# SafetySwitchBoard.net
KiCad netlist of a schematic drawn in EAGLE
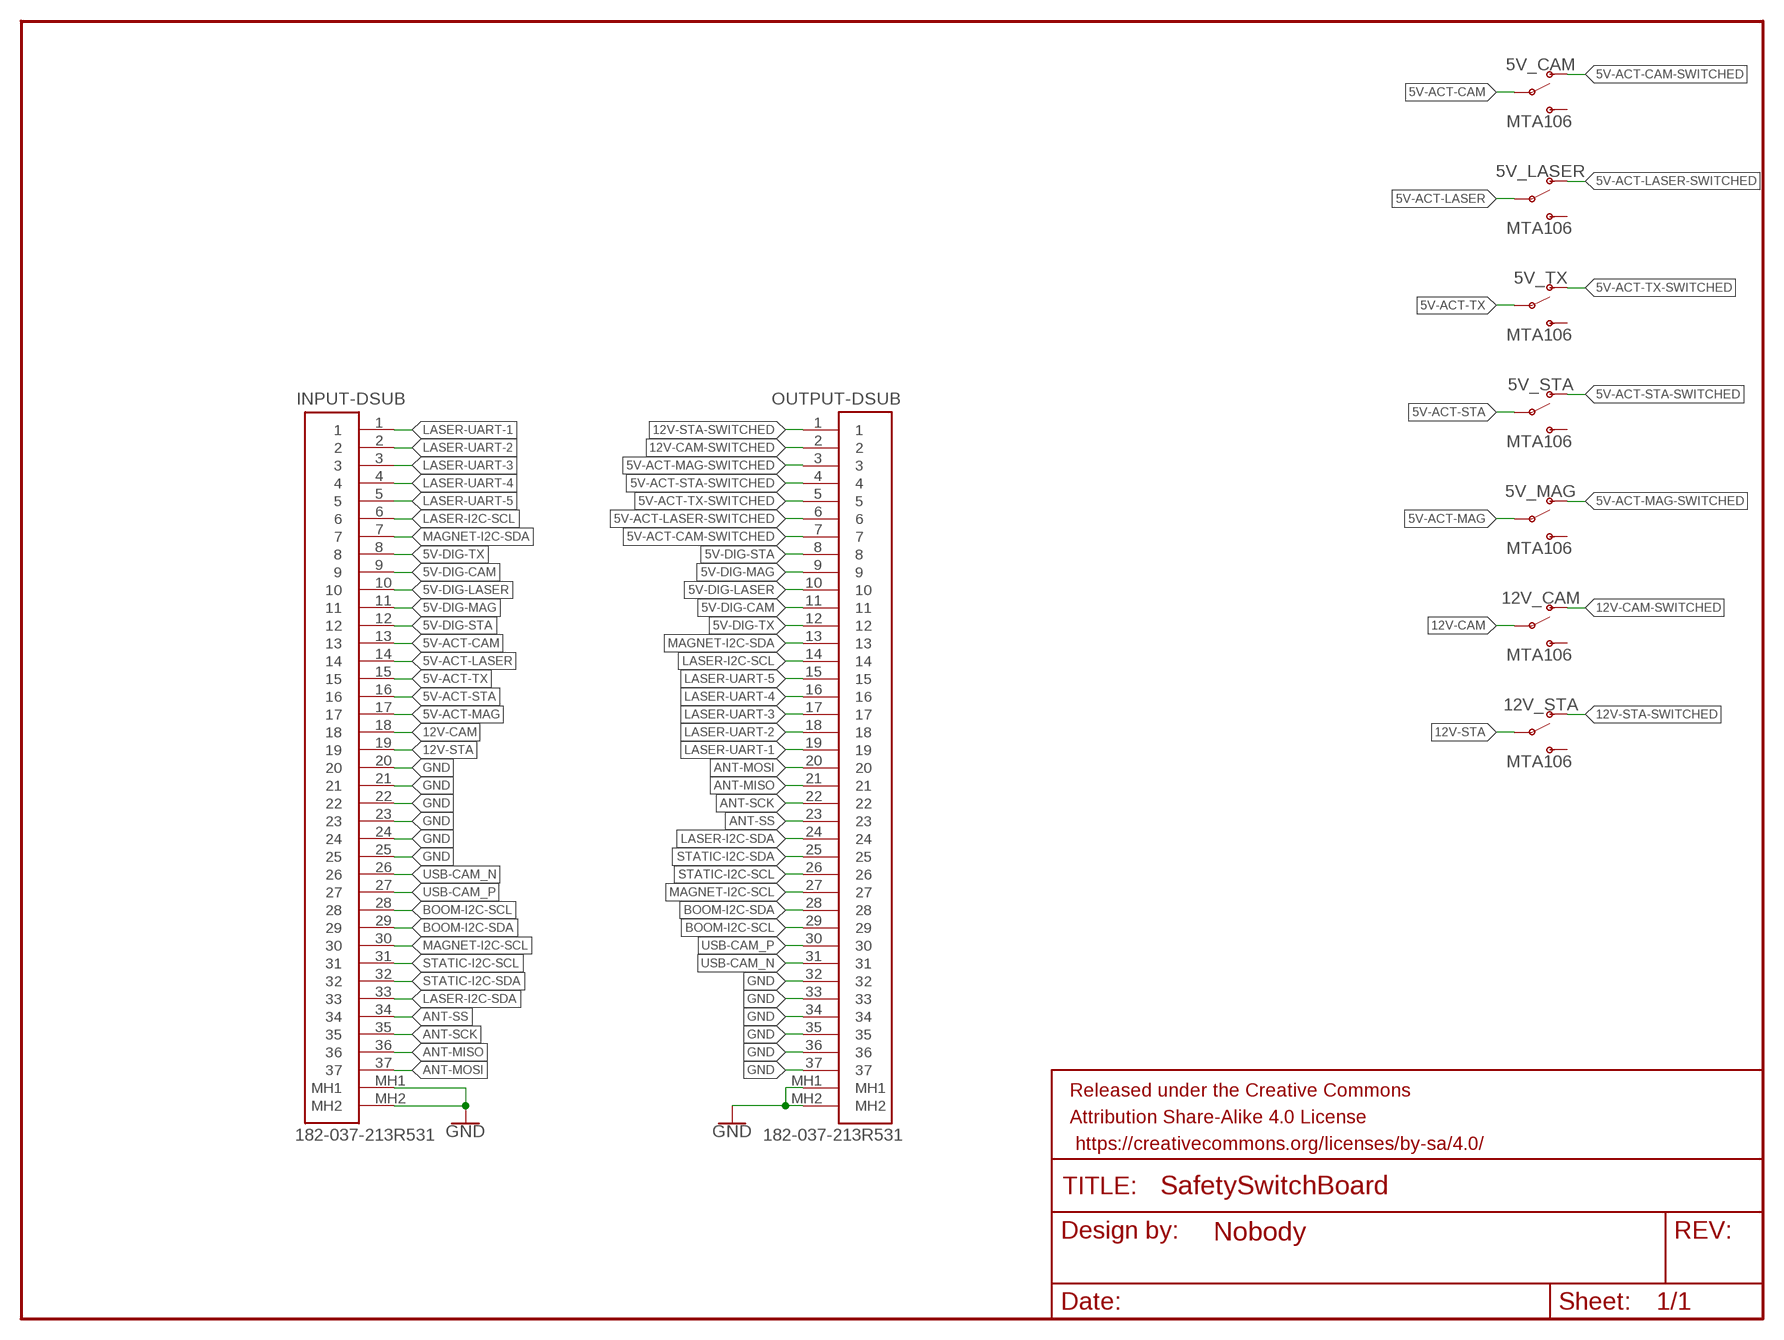
[diagram p0: schematic, sheet 1]

(export (version "E")
  (design (tool "Eeschema 10.0.6"))
  (components
    (comp (ref "5V_CAM")
      (value "MTA106")
      (footprint "eagle-import:MTA106")
      (libsource (lib "eagle-import") (part "MTA106"))
    )
    (comp (ref "5V_LASER")
      (value "MTA106")
      (footprint "eagle-import:MTA106")
      (libsource (lib "eagle-import") (part "MTA106"))
    )
    (comp (ref "5V_MAG")
      (value "MTA106")
      (footprint "eagle-import:MTA106")
      (libsource (lib "eagle-import") (part "MTA106"))
    )
    (comp (ref "5V_STA")
      (value "MTA106")
      (footprint "eagle-import:MTA106")
      (libsource (lib "eagle-import") (part "MTA106"))
    )
    (comp (ref "5V_TX")
      (value "MTA106")
      (footprint "eagle-import:MTA106")
      (libsource (lib "eagle-import") (part "MTA106"))
    )
    (comp (ref "12V_CAM")
      (value "MTA106")
      (footprint "eagle-import:MTA106")
      (libsource (lib "eagle-import") (part "MTA106"))
    )
    (comp (ref "12V_STA")
      (value "MTA106")
      (footprint "eagle-import:MTA106")
      (libsource (lib "eagle-import") (part "MTA106"))
    )
    (comp (ref "FRAME1")
      (value "FRAME-LETTERNO_PACKAGE")
      (footprint "eagle-import:DUMMY")
      (fields (field (name "DESIGNER") "Nobody"))
      (libsource (lib "eagle-import") (part "FRAME-LETTERNO_PACKAGE"))
    )
    (comp (ref "INPUT-DSUB")
      (value "182-037-213R531")
      (footprint "eagle-import:182-037-213R531")
      (fields
        (field (name "DIGI_KEY_PART_NUMBER") "182-37FE-ND")
        (field (name "MANUFACTURER") "NorComp Inc.")
        (field (name "CREATED_BY") "PCBLayout.com")
      )
      (libsource (lib "eagle-import") (part "182-037-213R531"))
    )
    (comp (ref "OUTPUT-DSUB")
      (value "182-037-213R531")
      (footprint "eagle-import:182-037-213R531")
      (fields
        (field (name "DIGI_KEY_PART_NUMBER") "182-37FE-ND")
        (field (name "MANUFACTURER") "NorComp Inc.")
        (field (name "CREATED_BY") "PCBLayout.com")
      )
      (libsource (lib "eagle-import") (part "182-037-213R531"))
    )
  )
  (nets
    (net (code "1") (name "5V-ACT-CAM") (class "Default")
      (node (ref "5V_CAM") (pin "P$1") (pinfunction "P_P$1") (pintype "passive"))
      (node (ref "INPUT-DSUB") (pin "13") (pinfunction "13_13") (pintype "passive"))
    )
    (net (code "2") (name "5V-ACT-CAM-SWITCHED") (class "Default")
      (node (ref "5V_CAM") (pin "P$2") (pinfunction "O_P$2") (pintype "passive"))
      (node (ref "OUTPUT-DSUB") (pin "7") (pinfunction "7_7") (pintype "passive"))
    )
    (net (code "3") (name "5V-ACT-LASER") (class "Default")
      (node (ref "5V_LASER") (pin "P$1") (pinfunction "P_P$1") (pintype "passive"))
      (node (ref "INPUT-DSUB") (pin "14") (pinfunction "14_14") (pintype "passive"))
    )
    (net (code "4") (name "5V-ACT-LASER-SWITCHED") (class "Default")
      (node (ref "5V_LASER") (pin "P$2") (pinfunction "O_P$2") (pintype "passive"))
      (node (ref "OUTPUT-DSUB") (pin "6") (pinfunction "6_6") (pintype "passive"))
    )
    (net (code "5") (name "5V-ACT-MAG") (class "Default")
      (node (ref "5V_MAG") (pin "P$1") (pinfunction "P_P$1") (pintype "passive"))
      (node (ref "INPUT-DSUB") (pin "17") (pinfunction "17_17") (pintype "passive"))
    )
    (net (code "6") (name "5V-ACT-MAG-SWITCHED") (class "Default")
      (node (ref "5V_MAG") (pin "P$2") (pinfunction "O_P$2") (pintype "passive"))
      (node (ref "OUTPUT-DSUB") (pin "3") (pinfunction "3_3") (pintype "passive"))
    )
    (net (code "7") (name "5V-ACT-STA") (class "Default")
      (node (ref "5V_STA") (pin "P$1") (pinfunction "P_P$1") (pintype "passive"))
      (node (ref "INPUT-DSUB") (pin "16") (pinfunction "16_16") (pintype "passive"))
    )
    (net (code "8") (name "5V-ACT-STA-SWITCHED") (class "Default")
      (node (ref "5V_STA") (pin "P$2") (pinfunction "O_P$2") (pintype "passive"))
      (node (ref "OUTPUT-DSUB") (pin "4") (pinfunction "4_4") (pintype "passive"))
    )
    (net (code "9") (name "5V-ACT-TX") (class "Default")
      (node (ref "5V_TX") (pin "P$1") (pinfunction "P_P$1") (pintype "passive"))
      (node (ref "INPUT-DSUB") (pin "15") (pinfunction "15_15") (pintype "passive"))
    )
    (net (code "10") (name "5V-ACT-TX-SWITCHED") (class "Default")
      (node (ref "5V_TX") (pin "P$2") (pinfunction "O_P$2") (pintype "passive"))
      (node (ref "OUTPUT-DSUB") (pin "5") (pinfunction "5_5") (pintype "passive"))
    )
    (net (code "11") (name "5V-DIG-CAM") (class "Default")
      (node (ref "INPUT-DSUB") (pin "9") (pinfunction "9_9") (pintype "passive"))
      (node (ref "OUTPUT-DSUB") (pin "11") (pinfunction "11_11") (pintype "passive"))
    )
    (net (code "12") (name "5V-DIG-LASER") (class "Default")
      (node (ref "INPUT-DSUB") (pin "10") (pinfunction "10_10") (pintype "passive"))
      (node (ref "OUTPUT-DSUB") (pin "10") (pinfunction "10_10") (pintype "passive"))
    )
    (net (code "13") (name "5V-DIG-MAG") (class "Default")
      (node (ref "INPUT-DSUB") (pin "11") (pinfunction "11_11") (pintype "passive"))
      (node (ref "OUTPUT-DSUB") (pin "9") (pinfunction "9_9") (pintype "passive"))
    )
    (net (code "14") (name "5V-DIG-STA") (class "Default")
      (node (ref "INPUT-DSUB") (pin "12") (pinfunction "12_12") (pintype "passive"))
      (node (ref "OUTPUT-DSUB") (pin "8") (pinfunction "8_8") (pintype "passive"))
    )
    (net (code "15") (name "5V-DIG-TX") (class "Default")
      (node (ref "INPUT-DSUB") (pin "8") (pinfunction "8_8") (pintype "passive"))
      (node (ref "OUTPUT-DSUB") (pin "12") (pinfunction "12_12") (pintype "passive"))
    )
    (net (code "16") (name "12V-CAM") (class "Default")
      (node (ref "12V_CAM") (pin "P$1") (pinfunction "P_P$1") (pintype "passive"))
      (node (ref "INPUT-DSUB") (pin "18") (pinfunction "18_18") (pintype "passive"))
    )
    (net (code "17") (name "12V-CAM-SWITCHED") (class "Default")
      (node (ref "12V_CAM") (pin "P$2") (pinfunction "O_P$2") (pintype "passive"))
      (node (ref "OUTPUT-DSUB") (pin "2") (pinfunction "2_2") (pintype "passive"))
    )
    (net (code "18") (name "12V-STA") (class "Default")
      (node (ref "12V_STA") (pin "P$1") (pinfunction "P_P$1") (pintype "passive"))
      (node (ref "INPUT-DSUB") (pin "19") (pinfunction "19_19") (pintype "passive"))
    )
    (net (code "19") (name "12V-STA-SWITCHED") (class "Default")
      (node (ref "12V_STA") (pin "P$2") (pinfunction "O_P$2") (pintype "passive"))
      (node (ref "OUTPUT-DSUB") (pin "1") (pinfunction "1_1") (pintype "passive"))
    )
    (net (code "20") (name "ANT-MISO") (class "Default")
      (node (ref "INPUT-DSUB") (pin "36") (pinfunction "36_36") (pintype "passive"))
      (node (ref "OUTPUT-DSUB") (pin "21") (pinfunction "21_21") (pintype "passive"))
    )
    (net (code "21") (name "ANT-MOSI") (class "Default")
      (node (ref "INPUT-DSUB") (pin "37") (pinfunction "37_37") (pintype "passive"))
      (node (ref "OUTPUT-DSUB") (pin "20") (pinfunction "20_20") (pintype "passive"))
    )
    (net (code "22") (name "ANT-SCK") (class "Default")
      (node (ref "INPUT-DSUB") (pin "35") (pinfunction "35_35") (pintype "passive"))
      (node (ref "OUTPUT-DSUB") (pin "22") (pinfunction "22_22") (pintype "passive"))
    )
    (net (code "23") (name "ANT-SS") (class "Default")
      (node (ref "INPUT-DSUB") (pin "34") (pinfunction "34_34") (pintype "passive"))
      (node (ref "OUTPUT-DSUB") (pin "23") (pinfunction "23_23") (pintype "passive"))
    )
    (net (code "24") (name "BOOM-I2C-SCL") (class "Default")
      (node (ref "INPUT-DSUB") (pin "28") (pinfunction "28_28") (pintype "passive"))
      (node (ref "OUTPUT-DSUB") (pin "29") (pinfunction "29_29") (pintype "passive"))
    )
    (net (code "25") (name "BOOM-I2C-SDA") (class "Default")
      (node (ref "INPUT-DSUB") (pin "29") (pinfunction "29_29") (pintype "passive"))
      (node (ref "OUTPUT-DSUB") (pin "28") (pinfunction "28_28") (pintype "passive"))
    )
    (net (code "26") (name "GND") (class "Default")
      (node (ref "INPUT-DSUB") (pin "20") (pinfunction "20_20") (pintype "passive"))
      (node (ref "INPUT-DSUB") (pin "21") (pinfunction "21_21") (pintype "passive"))
      (node (ref "INPUT-DSUB") (pin "22") (pinfunction "22_22") (pintype "passive"))
      (node (ref "INPUT-DSUB") (pin "23") (pinfunction "23_23") (pintype "passive"))
      (node (ref "INPUT-DSUB") (pin "24") (pinfunction "24_24") (pintype "passive"))
      (node (ref "INPUT-DSUB") (pin "25") (pinfunction "25_25") (pintype "passive"))
      (node (ref "INPUT-DSUB") (pin "MH1") (pinfunction "MH1_MH1") (pintype "passive"))
      (node (ref "INPUT-DSUB") (pin "MH2") (pinfunction "MH2_MH2") (pintype "passive"))
      (node (ref "OUTPUT-DSUB") (pin "32") (pinfunction "32_32") (pintype "passive"))
      (node (ref "OUTPUT-DSUB") (pin "33") (pinfunction "33_33") (pintype "passive"))
      (node (ref "OUTPUT-DSUB") (pin "34") (pinfunction "34_34") (pintype "passive"))
      (node (ref "OUTPUT-DSUB") (pin "35") (pinfunction "35_35") (pintype "passive"))
      (node (ref "OUTPUT-DSUB") (pin "36") (pinfunction "36_36") (pintype "passive"))
      (node (ref "OUTPUT-DSUB") (pin "37") (pinfunction "37_37") (pintype "passive"))
      (node (ref "OUTPUT-DSUB") (pin "MH1") (pinfunction "MH1_MH1") (pintype "passive"))
      (node (ref "OUTPUT-DSUB") (pin "MH2") (pinfunction "MH2_MH2") (pintype "passive"))
    )
    (net (code "27") (name "LASER-I2C-SCL") (class "Default")
      (node (ref "INPUT-DSUB") (pin "6") (pinfunction "6_6") (pintype "passive"))
      (node (ref "OUTPUT-DSUB") (pin "14") (pinfunction "14_14") (pintype "passive"))
    )
    (net (code "28") (name "LASER-I2C-SDA") (class "Default")
      (node (ref "INPUT-DSUB") (pin "33") (pinfunction "33_33") (pintype "passive"))
      (node (ref "OUTPUT-DSUB") (pin "24") (pinfunction "24_24") (pintype "passive"))
    )
    (net (code "29") (name "LASER-UART-1") (class "Default")
      (node (ref "INPUT-DSUB") (pin "1") (pinfunction "1_1") (pintype "passive"))
      (node (ref "OUTPUT-DSUB") (pin "19") (pinfunction "19_19") (pintype "passive"))
    )
    (net (code "30") (name "LASER-UART-2") (class "Default")
      (node (ref "INPUT-DSUB") (pin "2") (pinfunction "2_2") (pintype "passive"))
      (node (ref "OUTPUT-DSUB") (pin "18") (pinfunction "18_18") (pintype "passive"))
    )
    (net (code "31") (name "LASER-UART-3") (class "Default")
      (node (ref "INPUT-DSUB") (pin "3") (pinfunction "3_3") (pintype "passive"))
      (node (ref "OUTPUT-DSUB") (pin "17") (pinfunction "17_17") (pintype "passive"))
    )
    (net (code "32") (name "LASER-UART-4") (class "Default")
      (node (ref "INPUT-DSUB") (pin "4") (pinfunction "4_4") (pintype "passive"))
      (node (ref "OUTPUT-DSUB") (pin "16") (pinfunction "16_16") (pintype "passive"))
    )
    (net (code "33") (name "LASER-UART-5") (class "Default")
      (node (ref "INPUT-DSUB") (pin "5") (pinfunction "5_5") (pintype "passive"))
      (node (ref "OUTPUT-DSUB") (pin "15") (pinfunction "15_15") (pintype "passive"))
    )
    (net (code "34") (name "MAGNET-I2C-SCL") (class "Default")
      (node (ref "INPUT-DSUB") (pin "30") (pinfunction "30_30") (pintype "passive"))
      (node (ref "OUTPUT-DSUB") (pin "27") (pinfunction "27_27") (pintype "passive"))
    )
    (net (code "35") (name "MAGNET-I2C-SDA") (class "Default")
      (node (ref "INPUT-DSUB") (pin "7") (pinfunction "7_7") (pintype "passive"))
      (node (ref "OUTPUT-DSUB") (pin "13") (pinfunction "13_13") (pintype "passive"))
    )
    (net (code "36") (name "STATIC-I2C-SCL") (class "Default")
      (node (ref "INPUT-DSUB") (pin "31") (pinfunction "31_31") (pintype "passive"))
      (node (ref "OUTPUT-DSUB") (pin "26") (pinfunction "26_26") (pintype "passive"))
    )
    (net (code "37") (name "STATIC-I2C-SDA") (class "Default")
      (node (ref "INPUT-DSUB") (pin "32") (pinfunction "32_32") (pintype "passive"))
      (node (ref "OUTPUT-DSUB") (pin "25") (pinfunction "25_25") (pintype "passive"))
    )
    (net (code "38") (name "USB-CAM_N") (class "Default")
      (node (ref "INPUT-DSUB") (pin "26") (pinfunction "26_26") (pintype "passive"))
      (node (ref "OUTPUT-DSUB") (pin "31") (pinfunction "31_31") (pintype "passive"))
    )
    (net (code "39") (name "USB-CAM_P") (class "Default")
      (node (ref "INPUT-DSUB") (pin "27") (pinfunction "27_27") (pintype "passive"))
      (node (ref "OUTPUT-DSUB") (pin "30") (pinfunction "30_30") (pintype "passive"))
    )
    (net (code "40") (name "unconnected-(5V_CAM-S-PadP$3)") (class "Default")
      (node (ref "5V_CAM") (pin "P$3") (pinfunction "S_P$3") (pintype "passive"))
    )
    (net (code "41") (name "unconnected-(5V_LASER-S-PadP$3)") (class "Default")
      (node (ref "5V_LASER") (pin "P$3") (pinfunction "S_P$3") (pintype "passive"))
    )
    (net (code "42") (name "unconnected-(5V_MAG-S-PadP$3)") (class "Default")
      (node (ref "5V_MAG") (pin "P$3") (pinfunction "S_P$3") (pintype "passive"))
    )
    (net (code "43") (name "unconnected-(5V_STA-S-PadP$3)") (class "Default")
      (node (ref "5V_STA") (pin "P$3") (pinfunction "S_P$3") (pintype "passive"))
    )
    (net (code "44") (name "unconnected-(5V_TX-S-PadP$3)") (class "Default")
      (node (ref "5V_TX") (pin "P$3") (pinfunction "S_P$3") (pintype "passive"))
    )
    (net (code "45") (name "unconnected-(12V_CAM-S-PadP$3)") (class "Default")
      (node (ref "12V_CAM") (pin "P$3") (pinfunction "S_P$3") (pintype "passive"))
    )
    (net (code "46") (name "unconnected-(12V_STA-S-PadP$3)") (class "Default")
      (node (ref "12V_STA") (pin "P$3") (pinfunction "S_P$3") (pintype "passive"))
    )
  )
)
